# Main_NTC_Extension_5fach.net
KiCad netlist of a schematic drawn in Altium Designer
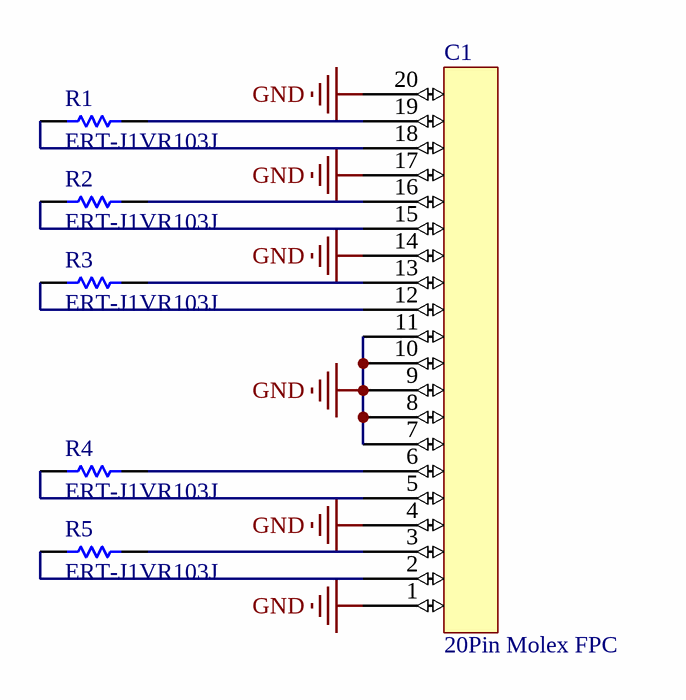
[diagram p0: Main_NTC_Extension_5fach.SchDoc]

(export (version "E")
  (design (tool "Eeschema 10.0.6"))
  (components
    (comp (ref "C1")
      (value "20Pin Molex FPC")
      (footprint "Molex 20 Pin FPC")
      (description "Flex PCB part for the Molex 20pin FCC")
      (libsource (lib "Integrated_LibraryLukas_New") (part "20Pin Molex FPC"))
    )
    (comp (ref "R1")
      (value "ERT-J1VR103J")
      (footprint "RESC1608X90X30ML15T20")
      (fields (field (name "MANUFACTURER") "Panasonic"))
      (libsource (lib "Altium Content Vault") (part "RES"))
    )
    (comp (ref "R2")
      (value "ERT-J1VR103J")
      (footprint "RESC1608X90X30ML15T20")
      (fields (field (name "MANUFACTURER") "Panasonic"))
      (libsource (lib "Altium Content Vault") (part "RES"))
    )
    (comp (ref "R3")
      (value "ERT-J1VR103J")
      (footprint "RESC1608X90X30ML15T20")
      (fields (field (name "MANUFACTURER") "Panasonic"))
      (libsource (lib "Altium Content Vault") (part "RES"))
    )
    (comp (ref "R4")
      (value "ERT-J1VR103J")
      (footprint "RESC1608X90X30ML15T20")
      (fields (field (name "MANUFACTURER") "Panasonic"))
      (libsource (lib "Altium Content Vault") (part "RES"))
    )
    (comp (ref "R5")
      (value "ERT-J1VR103J")
      (footprint "RESC1608X90X30ML15T20")
      (fields (field (name "MANUFACTURER") "Panasonic"))
      (libsource (lib "Altium Content Vault") (part "RES"))
    )
  )
  (nets
    (net (code "1") (name "GND") (class "Default")
      (node (ref "C1") (pin "1") (pintype "bidirectional"))
      (node (ref "C1") (pin "10") (pintype "bidirectional"))
      (node (ref "C1") (pin "11") (pintype "bidirectional"))
      (node (ref "C1") (pin "14") (pintype "bidirectional"))
      (node (ref "C1") (pin "17") (pintype "bidirectional"))
      (node (ref "C1") (pin "20") (pintype "bidirectional"))
      (node (ref "C1") (pin "4") (pintype "bidirectional"))
      (node (ref "C1") (pin "7") (pintype "bidirectional"))
      (node (ref "C1") (pin "8") (pintype "bidirectional"))
      (node (ref "C1") (pin "9") (pintype "bidirectional"))
    )
    (net (code "2") (name "Net-(C1-Pad2)") (class "Default")
      (node (ref "C1") (pin "2") (pintype "bidirectional"))
      (node (ref "R5") (pin "1") (pinfunction "1_1") (pintype "passive"))
    )
    (net (code "3") (name "Net-(C1-Pad3)") (class "Default")
      (node (ref "C1") (pin "3") (pintype "bidirectional"))
      (node (ref "R5") (pin "2") (pinfunction "2_2") (pintype "passive"))
    )
    (net (code "4") (name "Net-(C1-Pad5)") (class "Default")
      (node (ref "C1") (pin "5") (pintype "bidirectional"))
      (node (ref "R4") (pin "1") (pinfunction "1_1") (pintype "passive"))
    )
    (net (code "5") (name "Net-(C1-Pad6)") (class "Default")
      (node (ref "C1") (pin "6") (pintype "bidirectional"))
      (node (ref "R4") (pin "2") (pinfunction "2_2") (pintype "passive"))
    )
    (net (code "6") (name "Net-(C1-Pad12)") (class "Default")
      (node (ref "C1") (pin "12") (pintype "bidirectional"))
      (node (ref "R3") (pin "1") (pinfunction "1_1") (pintype "passive"))
    )
    (net (code "7") (name "Net-(C1-Pad13)") (class "Default")
      (node (ref "C1") (pin "13") (pintype "bidirectional"))
      (node (ref "R3") (pin "2") (pinfunction "2_2") (pintype "passive"))
    )
    (net (code "8") (name "Net-(C1-Pad15)") (class "Default")
      (node (ref "C1") (pin "15") (pintype "bidirectional"))
      (node (ref "R2") (pin "1") (pinfunction "1_1") (pintype "passive"))
    )
    (net (code "9") (name "Net-(C1-Pad16)") (class "Default")
      (node (ref "C1") (pin "16") (pintype "bidirectional"))
      (node (ref "R2") (pin "2") (pinfunction "2_2") (pintype "passive"))
    )
    (net (code "10") (name "Net-(C1-Pad18)") (class "Default")
      (node (ref "C1") (pin "18") (pintype "bidirectional"))
      (node (ref "R1") (pin "1") (pinfunction "1_1") (pintype "passive"))
    )
    (net (code "11") (name "Net-(C1-Pad19)") (class "Default")
      (node (ref "C1") (pin "19") (pintype "bidirectional"))
      (node (ref "R1") (pin "2") (pinfunction "2_2") (pintype "passive"))
    )
  )
)
